# sensor_single.net
KiCad netlist of a schematic drawn in Altium Designer
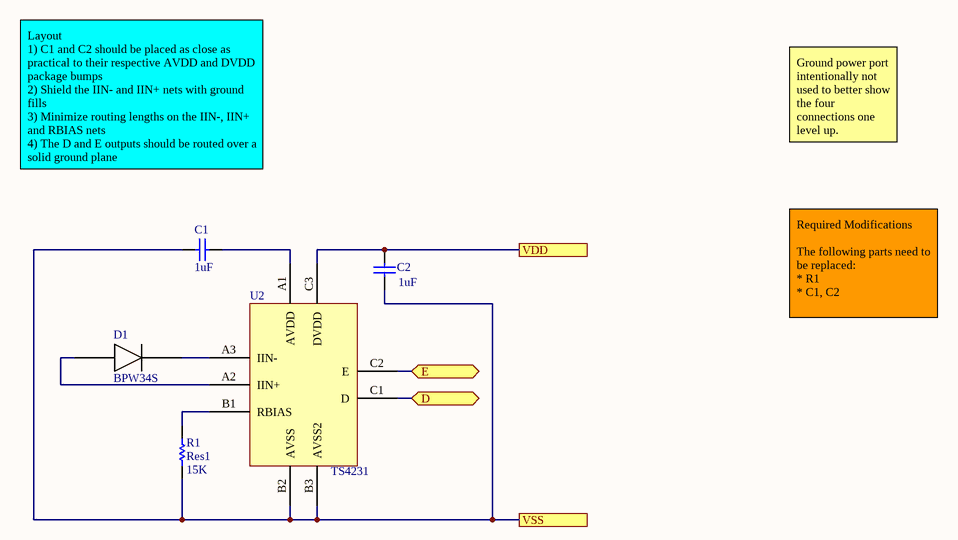
[diagram p0: sensor_single.SchDoc]

(export (version "E")
  (design (tool "Eeschema 10.0.6"))
  (components
    (comp (ref "C1")
      (value "1uF")
      (footprint "RAD-0.3")
      (description "Capacitor")
      (fields (field (name "Comment") "Cap") (field (name "PUBLISHER") "Altium Limited"))
      (libsource (lib "Miscellaneous Devices") (part "Cap"))
    )
    (comp (ref "C2")
      (value "1uF")
      (footprint "RAD-0.3")
      (description "Capacitor")
      (fields (field (name "Comment") "Cap") (field (name "PUBLISHER") "Altium Limited"))
      (libsource (lib "Miscellaneous Devices") (part "Cap"))
    )
    (comp (ref "D1")
      (value "BPW34S")
      (description "Silicon PIN Photodiode")
      (libsource (lib "CustomParts") (part "BPW34S"))
    )
    (comp (ref "R1")
      (value "Res1")
      (footprint "AXIAL-0.3")
      (description "Resistor")
      (fields (field (name "ALTIUM_VALUE") "15K") (field (name "PUBLISHER") "Altium Limited"))
      (libsource (lib "Miscellaneous Devices") (part "Res1"))
    )
    (comp (ref "U2")
      (value "TS4231")
      (description "Light to digital convertor for SteamVR 2.0 tracking.")
      (libsource (lib "CustomParts") (part "TS4231"))
    )
  )
  (nets
    (net (code "1") (name "/D") (class "Default")
      (node (ref "U2") (pin "C1") (pinfunction "D_C1") (pintype "passive"))
    )
    (net (code "2") (name "/E") (class "Default")
      (node (ref "U2") (pin "C2") (pinfunction "E_C2") (pintype "passive"))
    )
    (net (code "3") (name "/VDD") (class "Default")
      (node (ref "C2") (pin "1") (pinfunction "1_1") (pintype "passive"))
      (node (ref "U2") (pin "C3") (pinfunction "DVDD_C3") (pintype "passive"))
    )
    (net (code "4") (name "/VSS") (class "Default")
      (node (ref "C1") (pin "1") (pinfunction "1_1") (pintype "passive"))
      (node (ref "C2") (pin "2") (pinfunction "2_2") (pintype "passive"))
      (node (ref "R1") (pin "1") (pinfunction "1_1") (pintype "passive"))
      (node (ref "U2") (pin "B2") (pinfunction "AVSS_B2") (pintype "passive"))
      (node (ref "U2") (pin "B3") (pinfunction "AVSS2_B3") (pintype "passive"))
    )
    (net (code "5") (name "Net-(U2-AVDD)") (class "Default")
      (node (ref "C1") (pin "2") (pinfunction "2_2") (pintype "passive"))
      (node (ref "U2") (pin "A1") (pinfunction "AVDD_A1") (pintype "passive"))
    )
    (net (code "6") (name "Net-(U2-IIN+)") (class "Default")
      (node (ref "D1") (pin "A") (pinfunction "A_A") (pintype "passive"))
      (node (ref "U2") (pin "A2") (pinfunction "IIN+_A2") (pintype "passive"))
    )
    (net (code "7") (name "Net-(U2-IIN-)") (class "Default")
      (node (ref "D1") (pin "K") (pinfunction "K_K") (pintype "passive"))
      (node (ref "U2") (pin "A3") (pinfunction "IIN-_A3") (pintype "passive"))
    )
    (net (code "8") (name "Net-(U2-RBIAS)") (class "Default")
      (node (ref "R1") (pin "2") (pinfunction "2_2") (pintype "passive"))
      (node (ref "U2") (pin "B1") (pinfunction "RBIAS_B1") (pintype "passive"))
    )
  )
)
